# TSAL_Logic.net
KiCad netlist of a schematic drawn in Altium Designer
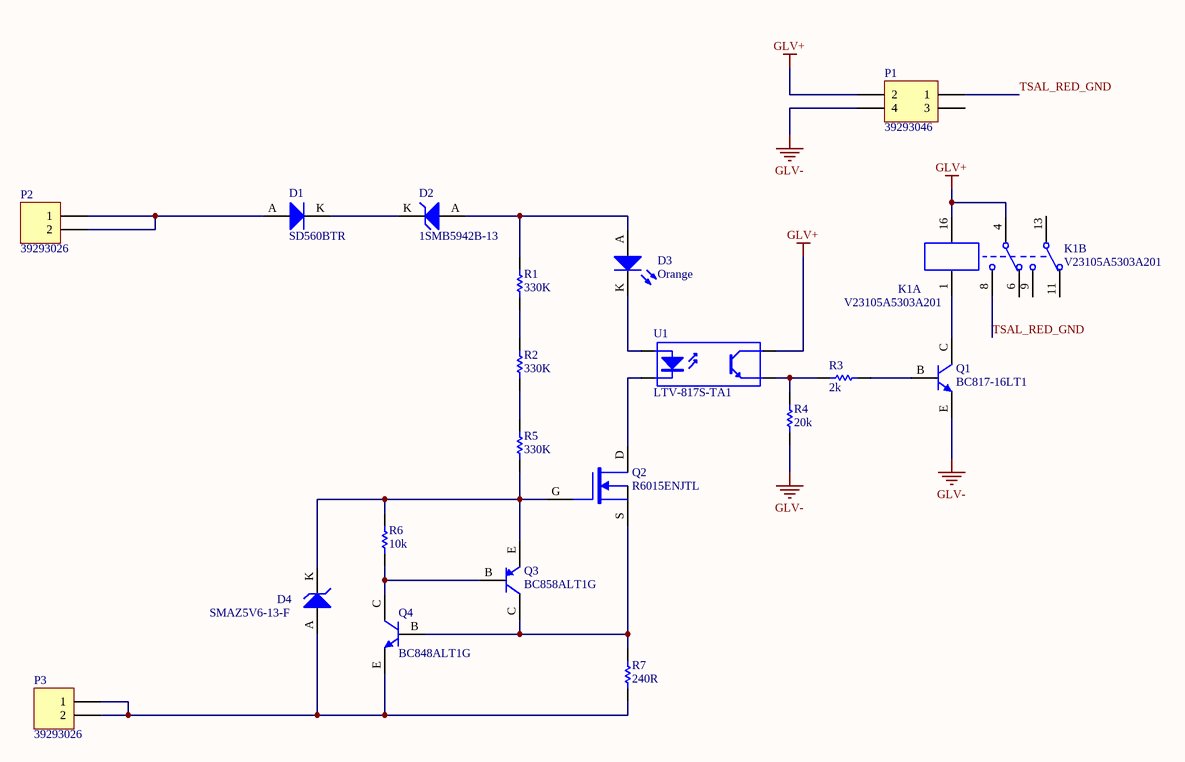
[diagram p0: TSAL_Logic.SchDoc]

(export (version "E")
  (design (tool "Eeschema 10.0.6"))
  (components
    (comp (ref "D1")
      (value "SD560BTR")
      (footprint "SMB Diode")
      (description "1.2V_F 600V 5A SMB")
      (fields
        (field (name "MANUFACTURER") "SMC Diode Solutions")
        (field (name "DIGIKEY PART NUMBER") "1655-1530-2-ND")
      )
      (libsource (lib "ts_20-standard-library") (part "Diode"))
    )
    (comp (ref "D2")
      (value "1SMB5942B-13")
      (footprint "DI SMB Diode")
      (description "DIODE ZENER 51V 3W SMB")
      (fields
        (field (name "MANUFACTURER") "Diodes Inc")
        (field (name "DIGIKEY PART NUMBER") "1SMB5942B-13DICT-ND")
      )
      (libsource (lib "ts_20-standard-library") (part "Zener Diode"))
    )
    (comp (ref "D3")
      (value "Orange")
      (footprint "0805 LED")
      (description "Orange LED Indication - Discrete 1.75V 0805 (2012 Metric)")
      (fields (field (name "PART NUMBER") "SML-211DTT86") (field (name "MANUFACTURER") "ROHM Semiconductor"))
      (libsource (lib "ts_20-standard-library") (part "LED"))
    )
    (comp (ref "D4")
      (value "SMAZ5V6-13-F")
      (footprint "DI SMA Diode")
      (description "DIODE ZENER 5.6V 1W SMA")
      (fields
        (field (name "MANUFACTURER") "Diodes Inc")
        (field (name "DIGIKEY PART NUMBER") "SMAZ5V6-FDICT-ND")
      )
      (libsource (lib "ts_20-standard-library") (part "Zener Diode"))
    )
    (comp (ref "K1")
      (value "V23105A5303A201")
      (footprint "TI 2-DIL")
      (description "RELAY TELECOM DPDT 3A 12V")
      (fields (field (name "MANUFACTURER") "TE Connectivity") (field (name "DIGIKEY PART NUMBER") "PB387-ND"))
      (libsource (lib "ts_20-standard-library") (part "V23105A5303A201"))
    )
    (comp (ref "P1")
      (value "39293046")
      (footprint "39293046")
      (fields (field (name "DIGIKEY PART NUMBER") "WM3844-ND") (field (name "CONTACT") "Tin"))
      (libsource (lib "ts_20-standard-connectors") (part "4"))
    )
    (comp (ref "P2")
      (value "39293026")
      (footprint "39293026")
      (fields (field (name "DIGIKEY PART NUMBER") "WM3843-ND") (field (name "CONTACT") "Tin"))
      (libsource (lib "ts_20-standard-connectors") (part "2"))
    )
    (comp (ref "P3")
      (value "39293026")
      (footprint "39293026")
      (fields (field (name "DIGIKEY PART NUMBER") "WM3843-ND") (field (name "CONTACT") "Tin"))
      (libsource (lib "ts_20-standard-connectors") (part "2"))
    )
    (comp (ref "Q1")
      (value "BC817-16LT1")
      (footprint "ON SOT-23 BJT")
      (description "300mW  BJT NPN Transistor")
      (fields
        (field (name "MANUFACTURER") "ON Semiconductor")
        (field (name "DIGIKEY PART NUMBER") "BC817-16LT1OSTR-ND")
      )
      (libsource (lib "ts_20-standard-library") (part "NPN"))
    )
    (comp (ref "Q2")
      (value "R6015ENJTL")
      (footprint "R TO-263 N-MOSFET")
      (description "MOSFET N-CH 600V 15A LPT")
      (fields
        (field (name "MANUFACTURER") "Rohm Semiconductor")
        (field (name "DIGIKEY PART NUMBER") "R6015ENJTLCT-ND")
        (field (name "PUBLISHER") "Altium Limited")
      )
      (libsource (lib "ts_20-standard-library") (part "MOSFET-N"))
    )
    (comp (ref "Q3")
      (value "BC858ALT1G")
      (footprint "ON TO-236-3 BJT")
      (description "TRANS PNP 30V 0.1A SOT-23")
      (fields
        (field (name "MANUFACTURER") "ON Semiconductor")
        (field (name "DIGIKEY PART NUMBER") "BC858ALT1GOSCT-ND")
      )
      (libsource (lib "ts_20-standard-library") (part "PNP"))
    )
    (comp (ref "Q4")
      (value "BC848ALT1G")
      (footprint "ON TO-236-3 BJT")
      (description "TRANS NPN 30V 0.1A SOT23")
      (fields
        (field (name "MANUFACTURER") "ON Semiconductor")
        (field (name "DIGIKEY PART NUMBER") "BC848ALT1GOSCT-ND")
      )
      (libsource (lib "ts_20-standard-library") (part "NPN"))
    )
    (comp (ref "R1")
      (value "330K")
      (footprint "VB 0204")
      (fields
        (field (name "PART NUMBER") "MMA02040C3303FB300")
        (field (name "MANUFACTURER") "Vishay Beyschlag")
        (field (name "TOLERANCE") "0.01")
      )
      (libsource (lib "ts_20-standard-library") (part "Resistor"))
    )
    (comp (ref "R2")
      (value "330K")
      (footprint "VB 0204")
      (fields
        (field (name "PART NUMBER") "MMA02040C3303FB300")
        (field (name "MANUFACTURER") "Vishay Beyschlag")
        (field (name "TOLERANCE") "0.01")
      )
      (libsource (lib "ts_20-standard-library") (part "Resistor"))
    )
    (comp (ref "R3")
      (value "2k")
      (footprint "0805")
      (fields
        (field (name "PART NUMBER") "RC0805FR072KL")
        (field (name "MANUFACTURER") "YAGEO")
        (field (name "TOLERANCE") "0.01")
      )
      (libsource (lib "ts_20-standard-library") (part "Resistor"))
    )
    (comp (ref "R4")
      (value "20k")
      (footprint "0805")
      (fields
        (field (name "PART NUMBER") "RC0805FR0720KL")
        (field (name "MANUFACTURER") "YAGEO")
        (field (name "TOLERANCE") "0.01")
      )
      (libsource (lib "ts_20-standard-library") (part "Resistor"))
    )
    (comp (ref "R5")
      (value "330K")
      (footprint "VB 0204")
      (fields
        (field (name "PART NUMBER") "MMA02040C3303FB300")
        (field (name "MANUFACTURER") "Vishay Beyschlag")
        (field (name "TOLERANCE") "0.01")
      )
      (libsource (lib "ts_20-standard-library") (part "Resistor"))
    )
    (comp (ref "R6")
      (value "10k")
      (footprint "0805")
      (fields
        (field (name "PART NUMBER") "RC0805FR0710KL")
        (field (name "MANUFACTURER") "YAGEO")
        (field (name "TOLERANCE") "0.01")
      )
      (libsource (lib "ts_20-standard-library") (part "Resistor"))
    )
    (comp (ref "R7")
      (value "240R")
      (footprint "0805")
      (fields
        (field (name "PART NUMBER") "RC0805FR07240RL")
        (field (name "MANUFACTURER") "YAGEO")
        (field (name "TOLERANCE") "0.01")
      )
      (libsource (lib "ts_20-standard-library") (part "Resistor"))
    )
    (comp (ref "U1")
      (value "LTV-817S-TA1")
      (footprint "ON 4-SMD")
      (description "35V 50ma Optocoupler (VF=1.2V)")
      (fields
        (field (name "MANUFACTURER") "Lite-On Inc")
        (field (name "DIGIKEY PART NUMBER") "160-1893-2-ND")
      )
      (libsource (lib "ts_20-standard-library") (part "LTV-817S-TA1"))
    )
  )
  (nets
    (net (code "1") (name "/TSAL_RED_GND") (class "Default")
      (node (ref "K1") (pin "8") (pinfunction "8_8") (pintype "passive"))
      (node (ref "P1") (pin "1") (pinfunction "1_1") (pintype "passive"))
    )
    (net (code "2") (name "GLV+") (class "Default")
      (node (ref "K1") (pin "16") (pinfunction "16_16") (pintype "passive"))
      (node (ref "K1") (pin "4") (pinfunction "4_4") (pintype "passive"))
      (node (ref "P1") (pin "2") (pinfunction "2_2") (pintype "passive"))
      (node (ref "U1") (pin "4") (pinfunction "C_4") (pintype "passive"))
    )
    (net (code "3") (name "GLV-") (class "Default")
      (node (ref "P1") (pin "4") (pinfunction "4_4") (pintype "passive"))
      (node (ref "Q1") (pin "E") (pinfunction "E_E") (pintype "passive"))
      (node (ref "R4") (pin "1") (pinfunction "1_1") (pintype "passive"))
    )
    (net (code "4") (name "Net-(D1-PadA)") (class "Default")
      (node (ref "D1") (pin "A") (pinfunction "A_A") (pintype "passive"))
      (node (ref "P2") (pin "1") (pinfunction "1_1") (pintype "passive"))
      (node (ref "P2") (pin "2") (pinfunction "2_2") (pintype "passive"))
    )
    (net (code "5") (name "Net-(D1-PadK)") (class "Default")
      (node (ref "D1") (pin "K") (pinfunction "K_K") (pintype "passive"))
      (node (ref "D2") (pin "K") (pinfunction "K_K") (pintype "passive"))
    )
    (net (code "6") (name "Net-(D2-PadA)") (class "Default")
      (node (ref "D2") (pin "A") (pinfunction "A_A") (pintype "passive"))
      (node (ref "D3") (pin "A") (pinfunction "A_A") (pintype "passive"))
      (node (ref "R1") (pin "2") (pinfunction "2_2") (pintype "passive"))
    )
    (net (code "7") (name "Net-(D4-PadA)") (class "Default")
      (node (ref "D4") (pin "A") (pinfunction "A_A") (pintype "passive"))
      (node (ref "P3") (pin "1") (pinfunction "1_1") (pintype "passive"))
      (node (ref "P3") (pin "2") (pinfunction "2_2") (pintype "passive"))
      (node (ref "Q4") (pin "E") (pinfunction "E_E") (pintype "passive"))
      (node (ref "R7") (pin "1") (pinfunction "1_1") (pintype "passive"))
    )
    (net (code "8") (name "Net-(D4-PadK)") (class "Default")
      (node (ref "D4") (pin "K") (pinfunction "K_K") (pintype "passive"))
      (node (ref "Q2") (pin "G") (pinfunction "G_G") (pintype "passive"))
      (node (ref "Q3") (pin "E") (pinfunction "E_E") (pintype "passive"))
      (node (ref "R5") (pin "1") (pinfunction "1_1") (pintype "passive"))
      (node (ref "R6") (pin "2") (pinfunction "2_2") (pintype "passive"))
    )
    (net (code "9") (name "Net-(K1-Pad1)") (class "Default")
      (node (ref "K1") (pin "1") (pinfunction "1_1") (pintype "passive"))
      (node (ref "Q1") (pin "C") (pinfunction "C_C") (pintype "passive"))
    )
    (net (code "10") (name "Net-(Q1-PadB)") (class "Default")
      (node (ref "Q1") (pin "B") (pinfunction "B_B") (pintype "passive"))
      (node (ref "R3") (pin "2") (pinfunction "2_2") (pintype "passive"))
    )
    (net (code "11") (name "Net-(Q2-PadS)") (class "Default")
      (node (ref "Q2") (pin "S") (pinfunction "S_S") (pintype "passive"))
      (node (ref "Q3") (pin "C") (pinfunction "C_C") (pintype "passive"))
      (node (ref "Q4") (pin "B") (pinfunction "B_B") (pintype "passive"))
      (node (ref "R7") (pin "2") (pinfunction "2_2") (pintype "passive"))
    )
    (net (code "12") (name "Net-(Q3-PadB)") (class "Default")
      (node (ref "Q3") (pin "B") (pinfunction "B_B") (pintype "passive"))
      (node (ref "Q4") (pin "C") (pinfunction "C_C") (pintype "passive"))
      (node (ref "R6") (pin "1") (pinfunction "1_1") (pintype "passive"))
    )
    (net (code "13") (name "Net-(R1-Pad1)") (class "Default")
      (node (ref "R1") (pin "1") (pinfunction "1_1") (pintype "passive"))
      (node (ref "R2") (pin "2") (pinfunction "2_2") (pintype "passive"))
    )
    (net (code "14") (name "Net-(R2-Pad1)") (class "Default")
      (node (ref "R2") (pin "1") (pinfunction "1_1") (pintype "passive"))
      (node (ref "R5") (pin "2") (pinfunction "2_2") (pintype "passive"))
    )
    (net (code "15") (name "Net-(U1-A)") (class "Default")
      (node (ref "D3") (pin "K") (pinfunction "K_K") (pintype "passive"))
      (node (ref "U1") (pin "1") (pinfunction "A_1") (pintype "passive"))
    )
    (net (code "16") (name "Net-(U1-E)") (class "Default")
      (node (ref "R3") (pin "1") (pinfunction "1_1") (pintype "passive"))
      (node (ref "R4") (pin "2") (pinfunction "2_2") (pintype "passive"))
      (node (ref "U1") (pin "3") (pinfunction "E_3") (pintype "passive"))
    )
    (net (code "17") (name "Net-(U1-K)") (class "Default")
      (node (ref "Q2") (pin "D") (pinfunction "D_D") (pintype "passive"))
      (node (ref "U1") (pin "2") (pinfunction "K_2") (pintype "passive"))
    )
    (net (code "18") (name "unconnected-(K1-Pad6)") (class "Default")
      (node (ref "K1") (pin "6") (pinfunction "6_6") (pintype "passive"))
    )
    (net (code "19") (name "unconnected-(K1-Pad9)") (class "Default")
      (node (ref "K1") (pin "9") (pinfunction "9_9") (pintype "passive"))
    )
    (net (code "20") (name "unconnected-(K1-Pad11)") (class "Default")
      (node (ref "K1") (pin "11") (pinfunction "11_11") (pintype "passive"))
    )
    (net (code "21") (name "unconnected-(K1-Pad13)") (class "Default")
      (node (ref "K1") (pin "13") (pinfunction "13_13") (pintype "passive"))
    )
    (net (code "22") (name "unconnected-(P1-Pad3)") (class "Default")
      (node (ref "P1") (pin "3") (pinfunction "3_3") (pintype "passive"))
    )
  )
)
